# B104C.net
KiCad netlist of a schematic drawn in EAGLE
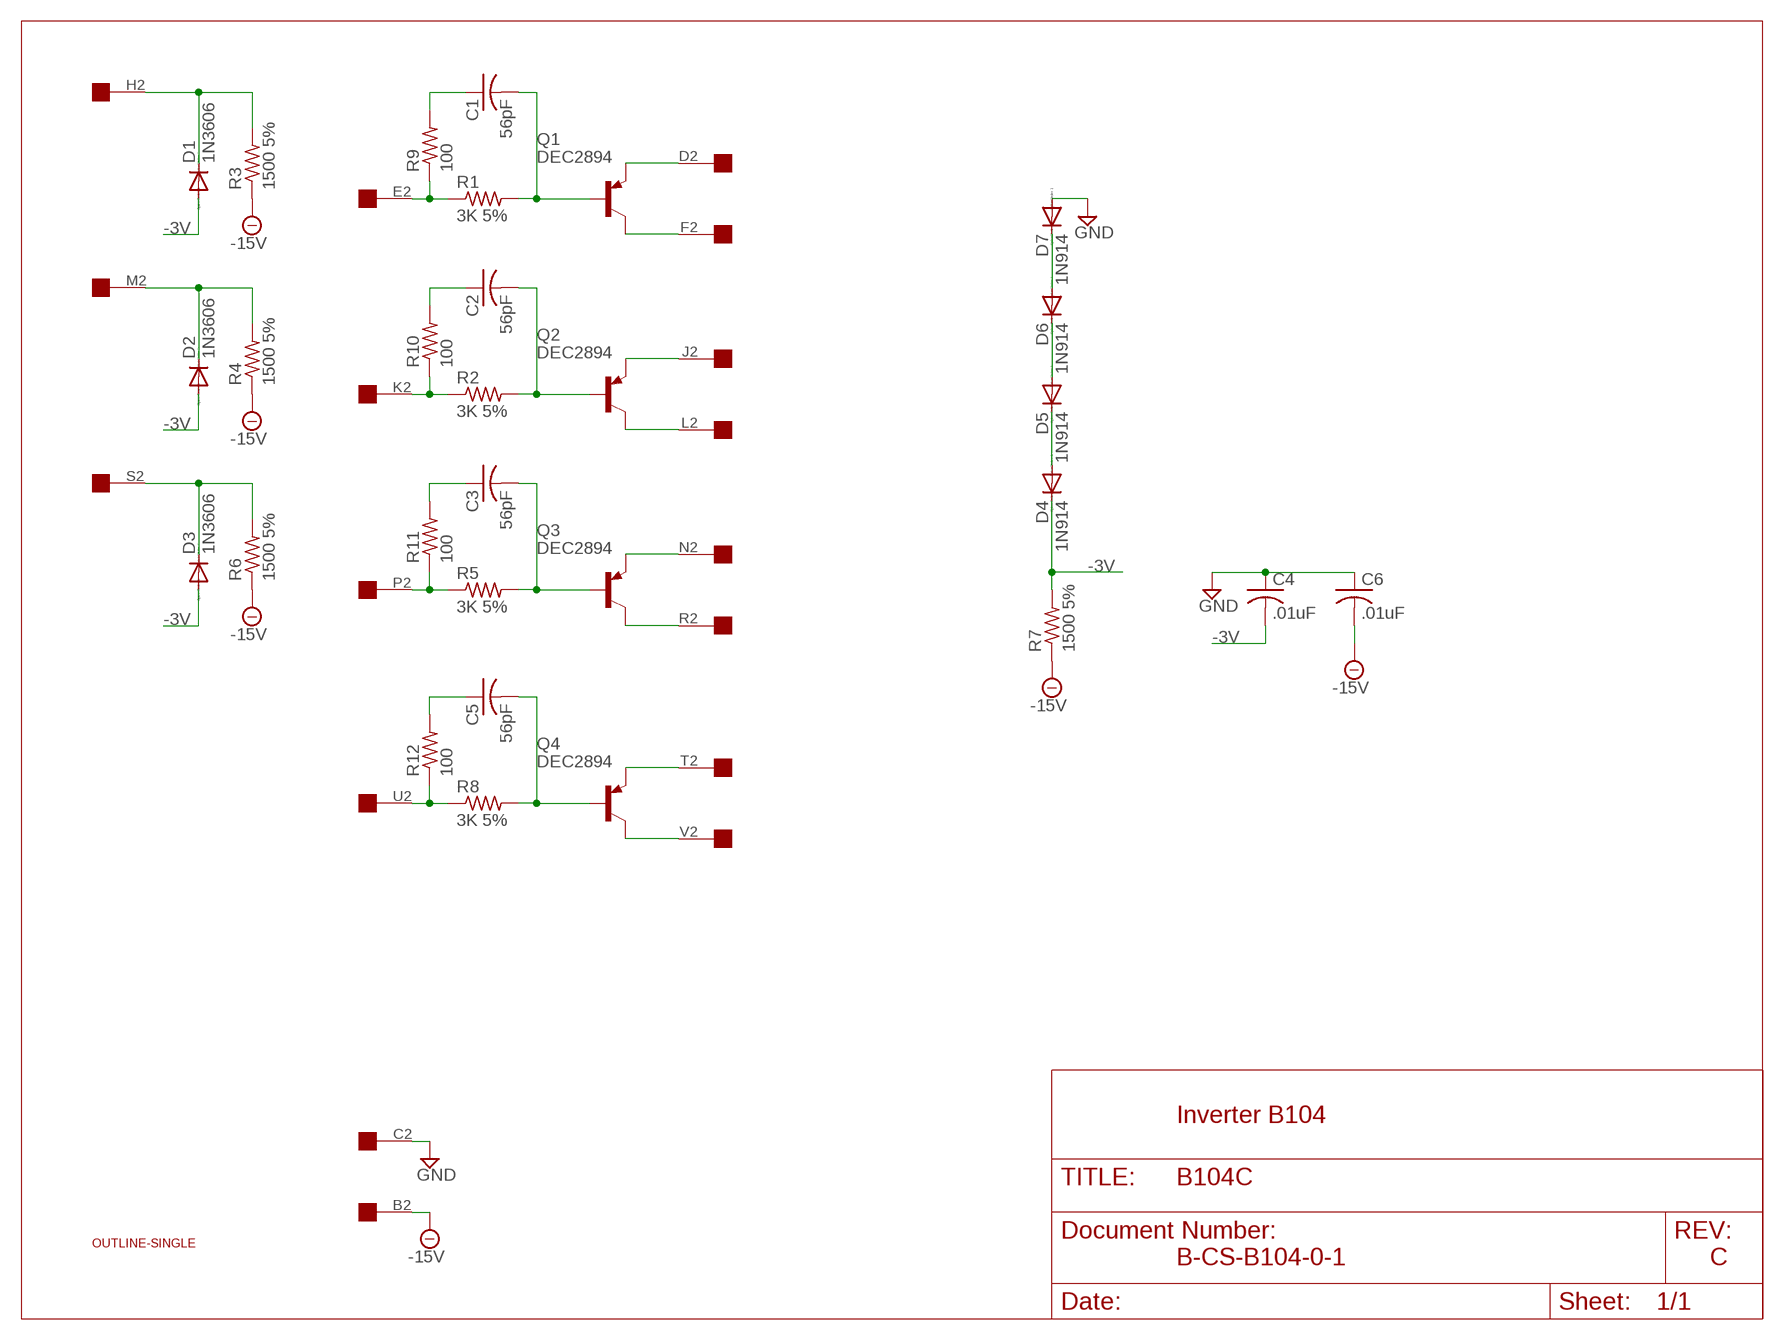
[diagram p0: schematic, sheet 1]

(export (version "E")
  (design (tool "Eeschema 10.0.6"))
  (components
    (comp (ref "C1")
      (value "56pF")
      (footprint "eagle-import:C150-054X183")
      (libsource (lib "eagle-import") (part "C-US150-054X183"))
    )
    (comp (ref "C2")
      (value "56pF")
      (footprint "eagle-import:C150-054X183")
      (libsource (lib "eagle-import") (part "C-US150-054X183"))
    )
    (comp (ref "C3")
      (value "56pF")
      (footprint "eagle-import:C150-054X183")
      (libsource (lib "eagle-import") (part "C-US150-054X183"))
    )
    (comp (ref "C4")
      (value ".01uF")
      (footprint "eagle-import:C150-054X183")
      (libsource (lib "eagle-import") (part "C-US150-054X183"))
    )
    (comp (ref "C5")
      (value "56pF")
      (footprint "eagle-import:C150-054X183")
      (libsource (lib "eagle-import") (part "C-US150-054X183"))
    )
    (comp (ref "C6")
      (value ".01uF")
      (footprint "eagle-import:C150-054X183")
      (libsource (lib "eagle-import") (part "C-US150-054X183"))
    )
    (comp (ref "D1")
      (value "1N3606")
      (footprint "eagle-import:DO35-10")
      (libsource (lib "eagle-import") (part "1N4148DO35-10"))
    )
    (comp (ref "D2")
      (value "1N3606")
      (footprint "eagle-import:DO35-10")
      (libsource (lib "eagle-import") (part "1N4148DO35-10"))
    )
    (comp (ref "D3")
      (value "1N3606")
      (footprint "eagle-import:DO35-10")
      (libsource (lib "eagle-import") (part "1N4148DO35-10"))
    )
    (comp (ref "D4")
      (value "1N914")
      (footprint "eagle-import:DO35-10")
      (libsource (lib "eagle-import") (part "1N4148DO35-10"))
    )
    (comp (ref "D5")
      (value "1N914")
      (footprint "eagle-import:DO35-10")
      (libsource (lib "eagle-import") (part "1N4148DO35-10"))
    )
    (comp (ref "D6")
      (value "1N914")
      (footprint "eagle-import:DO35-10")
      (libsource (lib "eagle-import") (part "1N4148DO35-10"))
    )
    (comp (ref "D7")
      (value "1N914")
      (footprint "eagle-import:DO35-10")
      (libsource (lib "eagle-import") (part "1N4148DO35-10"))
    )
    (comp (ref "Q1")
      (value "DEC2894")
      (footprint "eagle-import:TO39")
      (libsource (lib "eagle-import") (part "2N2904"))
    )
    (comp (ref "Q2")
      (value "DEC2894")
      (footprint "eagle-import:TO39")
      (libsource (lib "eagle-import") (part "2N2904"))
    )
    (comp (ref "Q3")
      (value "DEC2894")
      (footprint "eagle-import:TO39")
      (libsource (lib "eagle-import") (part "2N2904"))
    )
    (comp (ref "Q4")
      (value "DEC2894")
      (footprint "eagle-import:TO39")
      (libsource (lib "eagle-import") (part "2N2904"))
    )
    (comp (ref "R1")
      (value "3K 5%")
      (footprint "eagle-import:0207_10")
      (libsource (lib "eagle-import") (part "R-US_0207/10"))
    )
    (comp (ref "R2")
      (value "3K 5%")
      (footprint "eagle-import:0207_10")
      (libsource (lib "eagle-import") (part "R-US_0207/10"))
    )
    (comp (ref "R3")
      (value "1500 5%")
      (footprint "eagle-import:0207_10")
      (libsource (lib "eagle-import") (part "R-US_0207/10"))
    )
    (comp (ref "R4")
      (value "1500 5%")
      (footprint "eagle-import:0207_10")
      (libsource (lib "eagle-import") (part "R-US_0207/10"))
    )
    (comp (ref "R5")
      (value "3K 5%")
      (footprint "eagle-import:0207_10")
      (libsource (lib "eagle-import") (part "R-US_0207/10"))
    )
    (comp (ref "R6")
      (value "1500 5%")
      (footprint "eagle-import:0207_10")
      (libsource (lib "eagle-import") (part "R-US_0207/10"))
    )
    (comp (ref "R7")
      (value "1500 5%")
      (footprint "eagle-import:0207_10")
      (libsource (lib "eagle-import") (part "R-US_0207/10"))
    )
    (comp (ref "R8")
      (value "3K 5%")
      (footprint "eagle-import:0207_10")
      (libsource (lib "eagle-import") (part "R-US_0207/10"))
    )
    (comp (ref "R9")
      (value "100")
      (footprint "eagle-import:0207_10")
      (libsource (lib "eagle-import") (part "R-US_0207/10"))
    )
    (comp (ref "R10")
      (value "100")
      (footprint "eagle-import:0207_10")
      (libsource (lib "eagle-import") (part "R-US_0207/10"))
    )
    (comp (ref "R11")
      (value "100")
      (footprint "eagle-import:0207_10")
      (libsource (lib "eagle-import") (part "R-US_0207/10"))
    )
    (comp (ref "R12")
      (value "100")
      (footprint "eagle-import:0207_10")
      (libsource (lib "eagle-import") (part "R-US_0207/10"))
    )
    (comp (ref "U$1")
      (value "OUTLINE-SINGLE")
      (footprint "eagle-import:SINGLE")
      (libsource (lib "eagle-import") (part "OUTLINE-SINGLE"))
    )
    (comp (ref "U$2")
      (value "EDGE-1")
      (footprint "eagle-import:EDGE-CON1")
      (libsource (lib "eagle-import") (part "EDGE-1"))
    )
  )
  (nets
    (net (code "1") (name "-15V") (class "Default")
      (node (ref "C6") (pin "2") (pinfunction "2_2") (pintype "passive"))
      (node (ref "R3") (pin "1") (pinfunction "1_1") (pintype "passive"))
      (node (ref "R4") (pin "1") (pinfunction "1_1") (pintype "passive"))
      (node (ref "R6") (pin "1") (pinfunction "1_1") (pintype "passive"))
      (node (ref "R7") (pin "1") (pinfunction "1_1") (pintype "passive"))
      (node (ref "U$2") (pin "B2") (pinfunction "1_B2") (pintype "bidirectional"))
    )
    (net (code "2") (name "/-3V") (class "Default")
      (node (ref "C4") (pin "2") (pinfunction "2_2") (pintype "passive"))
      (node (ref "D1") (pin "A") (pinfunction "A_A") (pintype "passive"))
      (node (ref "D2") (pin "A") (pinfunction "A_A") (pintype "passive"))
      (node (ref "D3") (pin "A") (pinfunction "A_A") (pintype "passive"))
      (node (ref "D4") (pin "C") (pinfunction "C_C") (pintype "passive"))
      (node (ref "R7") (pin "2") (pinfunction "2_2") (pintype "passive"))
    )
    (net (code "3") (name "GND") (class "Default")
      (node (ref "C4") (pin "1") (pinfunction "1_1") (pintype "passive"))
      (node (ref "C6") (pin "1") (pinfunction "1_1") (pintype "passive"))
      (node (ref "D7") (pin "A") (pinfunction "A_A") (pintype "passive"))
      (node (ref "U$2") (pin "C2") (pinfunction "1_C2") (pintype "bidirectional"))
    )
    (net (code "4") (name "Net-(C1-Pad1)") (class "Default")
      (node (ref "C1") (pin "1") (pinfunction "1_1") (pintype "passive"))
      (node (ref "R9") (pin "2") (pinfunction "2_2") (pintype "passive"))
    )
    (net (code "5") (name "Net-(C2-Pad1)") (class "Default")
      (node (ref "C2") (pin "1") (pinfunction "1_1") (pintype "passive"))
      (node (ref "R10") (pin "2") (pinfunction "2_2") (pintype "passive"))
    )
    (net (code "6") (name "Net-(C3-Pad1)") (class "Default")
      (node (ref "C3") (pin "1") (pinfunction "1_1") (pintype "passive"))
      (node (ref "R11") (pin "2") (pinfunction "2_2") (pintype "passive"))
    )
    (net (code "7") (name "Net-(C5-Pad1)") (class "Default")
      (node (ref "C5") (pin "1") (pinfunction "1_1") (pintype "passive"))
      (node (ref "R12") (pin "2") (pinfunction "2_2") (pintype "passive"))
    )
    (net (code "8") (name "Net-(D4-PadA)") (class "Default")
      (node (ref "D4") (pin "A") (pinfunction "A_A") (pintype "passive"))
      (node (ref "D5") (pin "C") (pinfunction "C_C") (pintype "passive"))
    )
    (net (code "9") (name "Net-(D5-PadA)") (class "Default")
      (node (ref "D5") (pin "A") (pinfunction "A_A") (pintype "passive"))
      (node (ref "D6") (pin "C") (pinfunction "C_C") (pintype "passive"))
    )
    (net (code "10") (name "Net-(D6-PadA)") (class "Default")
      (node (ref "D6") (pin "A") (pinfunction "A_A") (pintype "passive"))
      (node (ref "D7") (pin "C") (pinfunction "C_C") (pintype "passive"))
    )
    (net (code "11") (name "Net-(Q1-B)") (class "Default")
      (node (ref "C1") (pin "2") (pinfunction "2_2") (pintype "passive"))
      (node (ref "Q1") (pin "2") (pinfunction "B_2") (pintype "passive"))
      (node (ref "R1") (pin "2") (pinfunction "2_2") (pintype "passive"))
    )
    (net (code "12") (name "Net-(Q1-C)") (class "Default")
      (node (ref "Q1") (pin "3") (pinfunction "C_3") (pintype "passive"))
      (node (ref "U$2") (pin "F2") (pinfunction "1_F2") (pintype "bidirectional"))
    )
    (net (code "13") (name "Net-(Q1-E)") (class "Default")
      (node (ref "Q1") (pin "1") (pinfunction "E_1") (pintype "passive"))
      (node (ref "U$2") (pin "D2") (pinfunction "1_D2") (pintype "bidirectional"))
    )
    (net (code "14") (name "Net-(Q2-B)") (class "Default")
      (node (ref "C2") (pin "2") (pinfunction "2_2") (pintype "passive"))
      (node (ref "Q2") (pin "2") (pinfunction "B_2") (pintype "passive"))
      (node (ref "R2") (pin "2") (pinfunction "2_2") (pintype "passive"))
    )
    (net (code "15") (name "Net-(Q2-C)") (class "Default")
      (node (ref "Q2") (pin "3") (pinfunction "C_3") (pintype "passive"))
      (node (ref "U$2") (pin "L2") (pinfunction "1_L2") (pintype "bidirectional"))
    )
    (net (code "16") (name "Net-(Q2-E)") (class "Default")
      (node (ref "Q2") (pin "1") (pinfunction "E_1") (pintype "passive"))
      (node (ref "U$2") (pin "J2") (pinfunction "1_J2") (pintype "bidirectional"))
    )
    (net (code "17") (name "Net-(Q3-B)") (class "Default")
      (node (ref "C3") (pin "2") (pinfunction "2_2") (pintype "passive"))
      (node (ref "Q3") (pin "2") (pinfunction "B_2") (pintype "passive"))
      (node (ref "R5") (pin "2") (pinfunction "2_2") (pintype "passive"))
    )
    (net (code "18") (name "Net-(Q3-C)") (class "Default")
      (node (ref "Q3") (pin "3") (pinfunction "C_3") (pintype "passive"))
      (node (ref "U$2") (pin "R2") (pinfunction "1_R2") (pintype "bidirectional"))
    )
    (net (code "19") (name "Net-(Q3-E)") (class "Default")
      (node (ref "Q3") (pin "1") (pinfunction "E_1") (pintype "passive"))
      (node (ref "U$2") (pin "N2") (pinfunction "1_N2") (pintype "bidirectional"))
    )
    (net (code "20") (name "Net-(Q4-B)") (class "Default")
      (node (ref "C5") (pin "2") (pinfunction "2_2") (pintype "passive"))
      (node (ref "Q4") (pin "2") (pinfunction "B_2") (pintype "passive"))
      (node (ref "R8") (pin "2") (pinfunction "2_2") (pintype "passive"))
    )
    (net (code "21") (name "Net-(Q4-C)") (class "Default")
      (node (ref "Q4") (pin "3") (pinfunction "C_3") (pintype "passive"))
      (node (ref "U$2") (pin "V2") (pinfunction "1_V2") (pintype "bidirectional"))
    )
    (net (code "22") (name "Net-(Q4-E)") (class "Default")
      (node (ref "Q4") (pin "1") (pinfunction "E_1") (pintype "passive"))
      (node (ref "U$2") (pin "T2") (pinfunction "1_T2") (pintype "bidirectional"))
    )
    (net (code "23") (name "Net-(U$2E-1)") (class "Default")
      (node (ref "R1") (pin "1") (pinfunction "1_1") (pintype "passive"))
      (node (ref "R9") (pin "1") (pinfunction "1_1") (pintype "passive"))
      (node (ref "U$2") (pin "E2") (pinfunction "1_E2") (pintype "bidirectional"))
    )
    (net (code "24") (name "Net-(U$2G-1)") (class "Default")
      (node (ref "D1") (pin "C") (pinfunction "C_C") (pintype "passive"))
      (node (ref "R3") (pin "2") (pinfunction "2_2") (pintype "passive"))
      (node (ref "U$2") (pin "H2") (pinfunction "1_H2") (pintype "bidirectional"))
    )
    (net (code "25") (name "Net-(U$2I-1)") (class "Default")
      (node (ref "R10") (pin "1") (pinfunction "1_1") (pintype "passive"))
      (node (ref "R2") (pin "1") (pinfunction "1_1") (pintype "passive"))
      (node (ref "U$2") (pin "K2") (pinfunction "1_K2") (pintype "bidirectional"))
    )
    (net (code "26") (name "Net-(U$2K-1)") (class "Default")
      (node (ref "D2") (pin "C") (pinfunction "C_C") (pintype "passive"))
      (node (ref "R4") (pin "2") (pinfunction "2_2") (pintype "passive"))
      (node (ref "U$2") (pin "M2") (pinfunction "1_M2") (pintype "bidirectional"))
    )
    (net (code "27") (name "Net-(U$2M-1)") (class "Default")
      (node (ref "R11") (pin "1") (pinfunction "1_1") (pintype "passive"))
      (node (ref "R5") (pin "1") (pinfunction "1_1") (pintype "passive"))
      (node (ref "U$2") (pin "P2") (pinfunction "1_P2") (pintype "bidirectional"))
    )
    (net (code "28") (name "Net-(U$2O-1)") (class "Default")
      (node (ref "D3") (pin "C") (pinfunction "C_C") (pintype "passive"))
      (node (ref "R6") (pin "2") (pinfunction "2_2") (pintype "passive"))
      (node (ref "U$2") (pin "S2") (pinfunction "1_S2") (pintype "bidirectional"))
    )
    (net (code "29") (name "Net-(U$2Q-1)") (class "Default")
      (node (ref "R12") (pin "1") (pinfunction "1_1") (pintype "passive"))
      (node (ref "R8") (pin "1") (pinfunction "1_1") (pintype "passive"))
      (node (ref "U$2") (pin "U2") (pinfunction "1_U2") (pintype "bidirectional"))
    )
  )
)
